# sketch.net
KiCad netlist of a schematic drawn in EAGLE
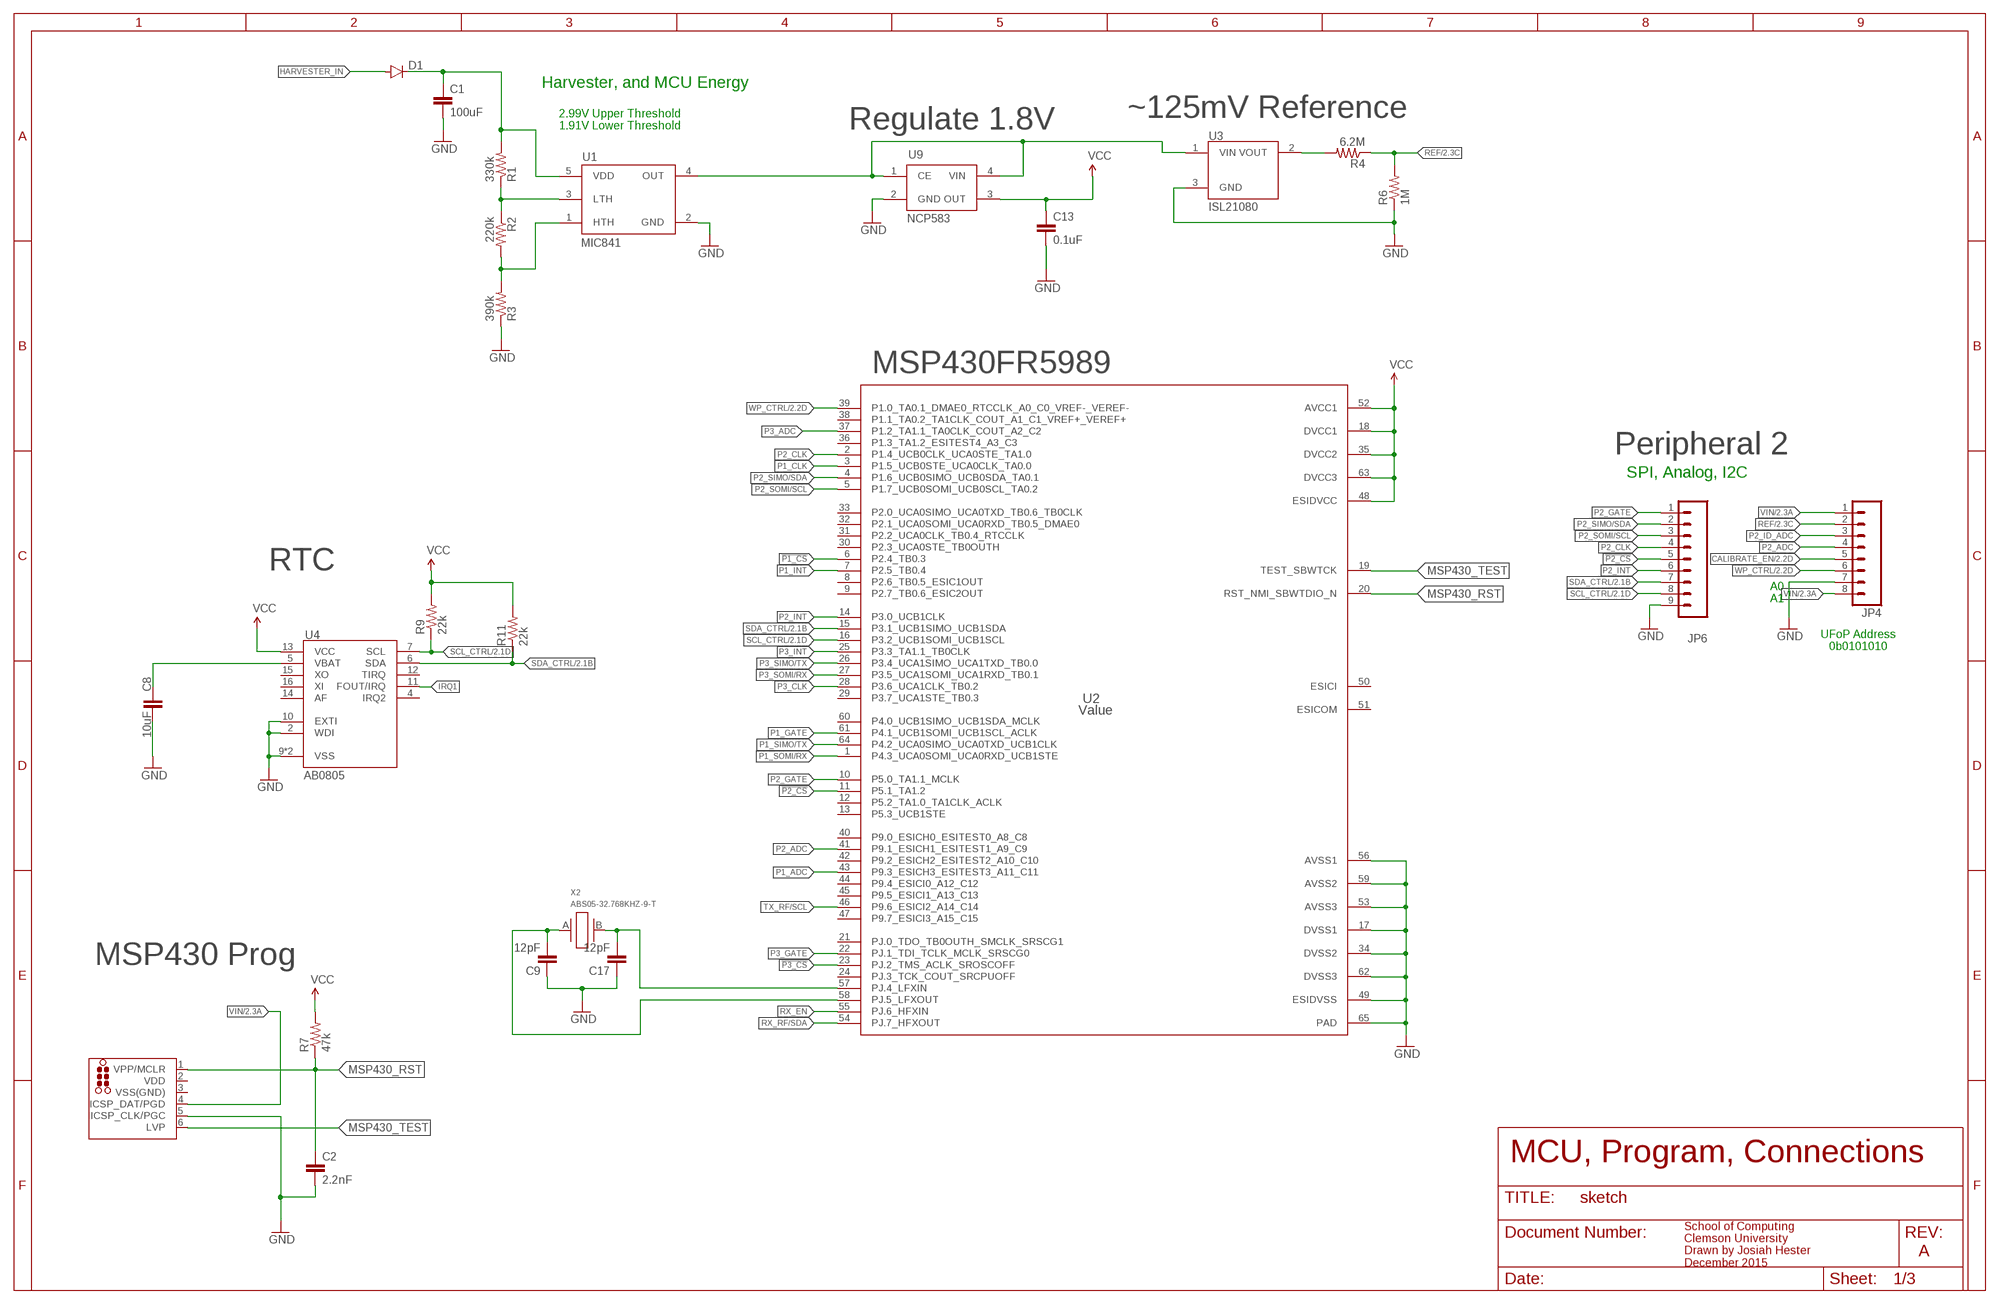
[diagram p0: schematic, sheet 1]
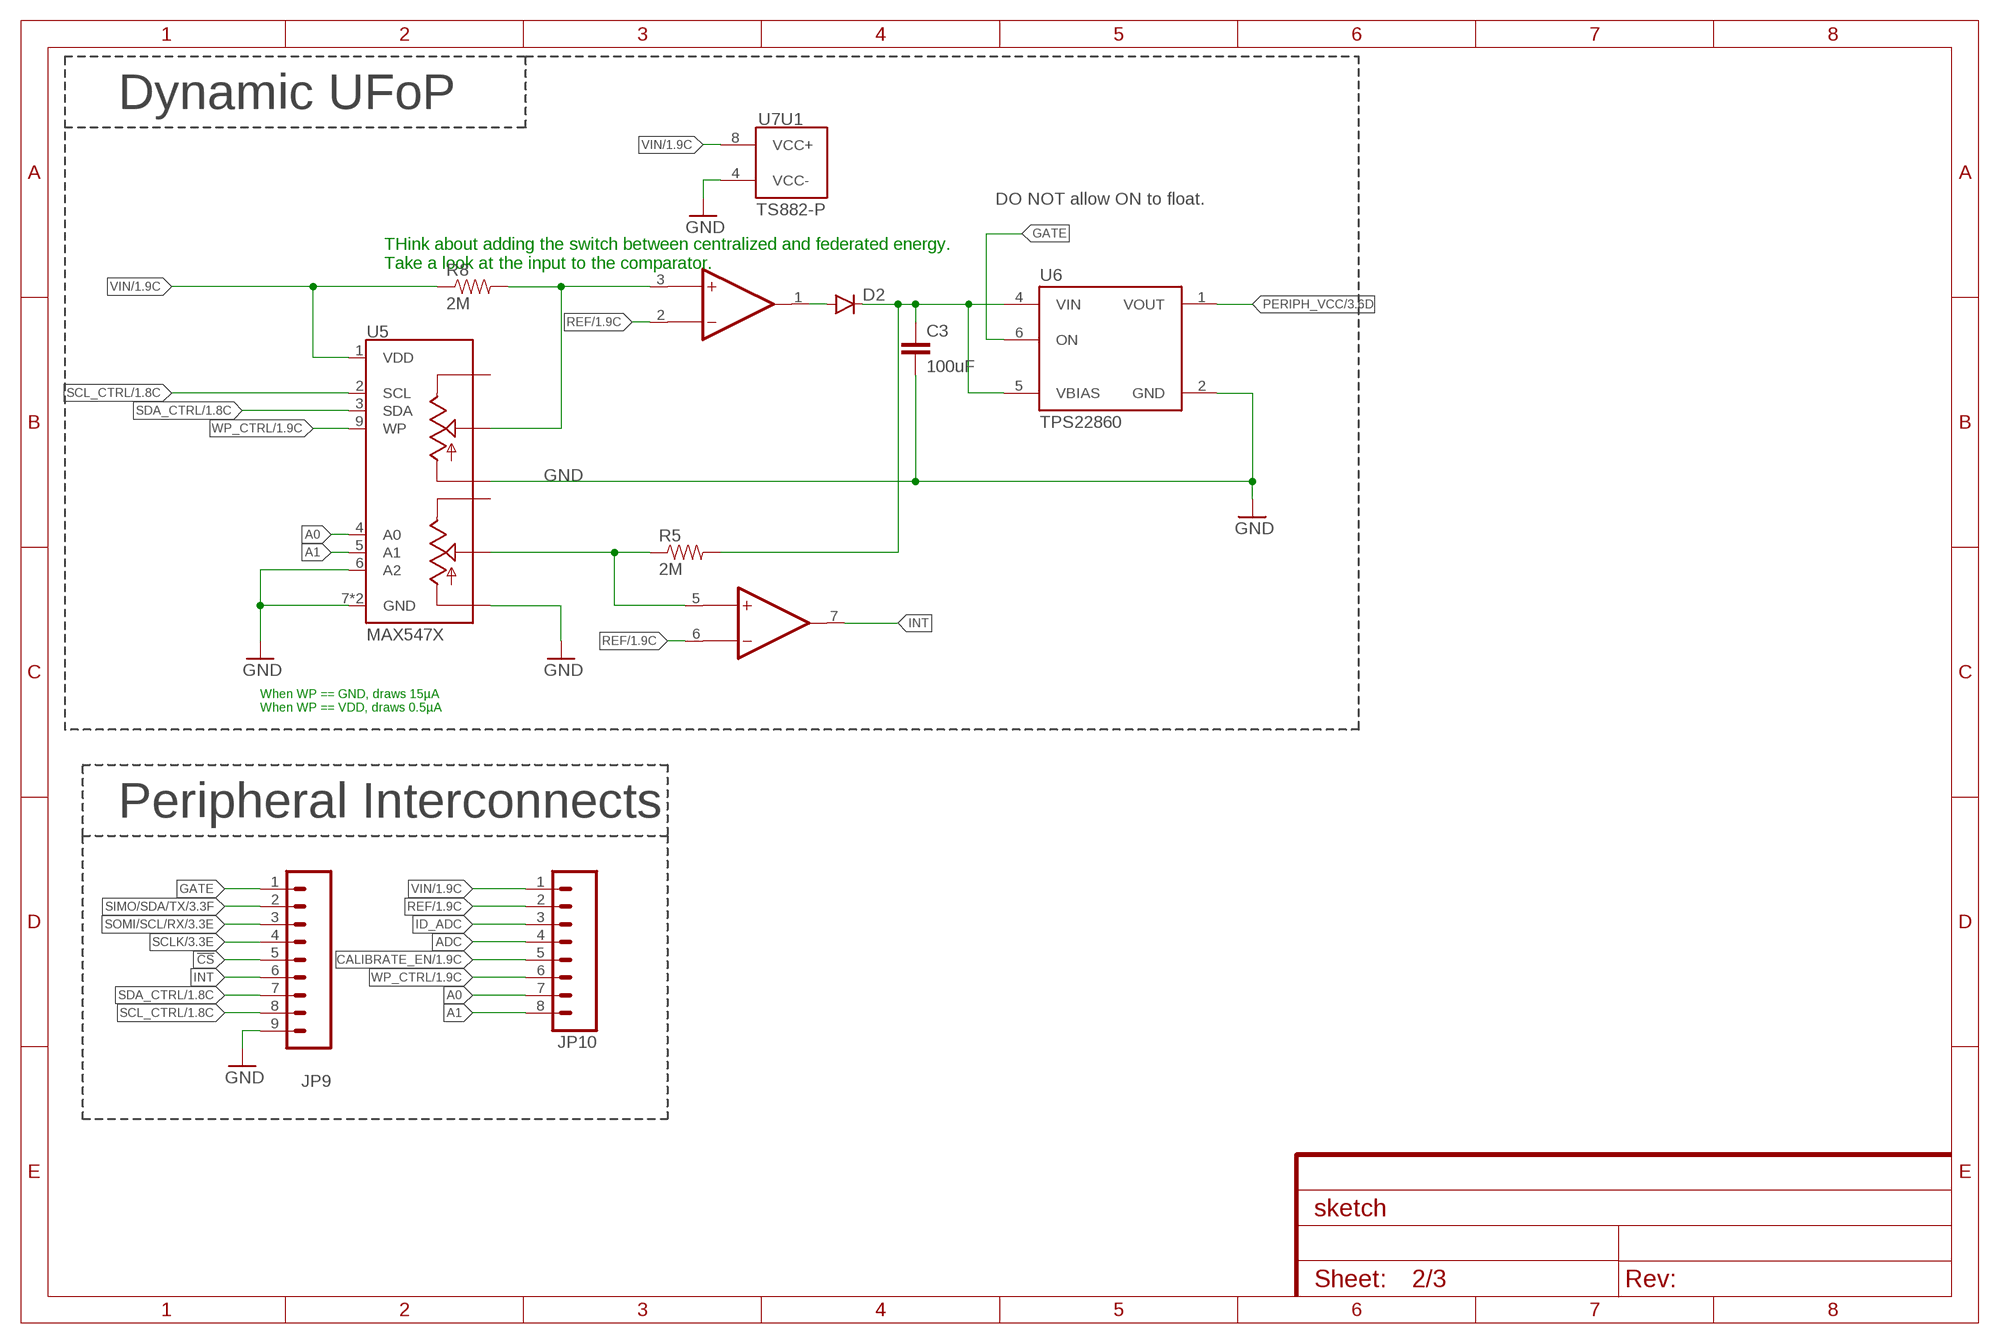
[diagram p1: schematic, sheet 2]
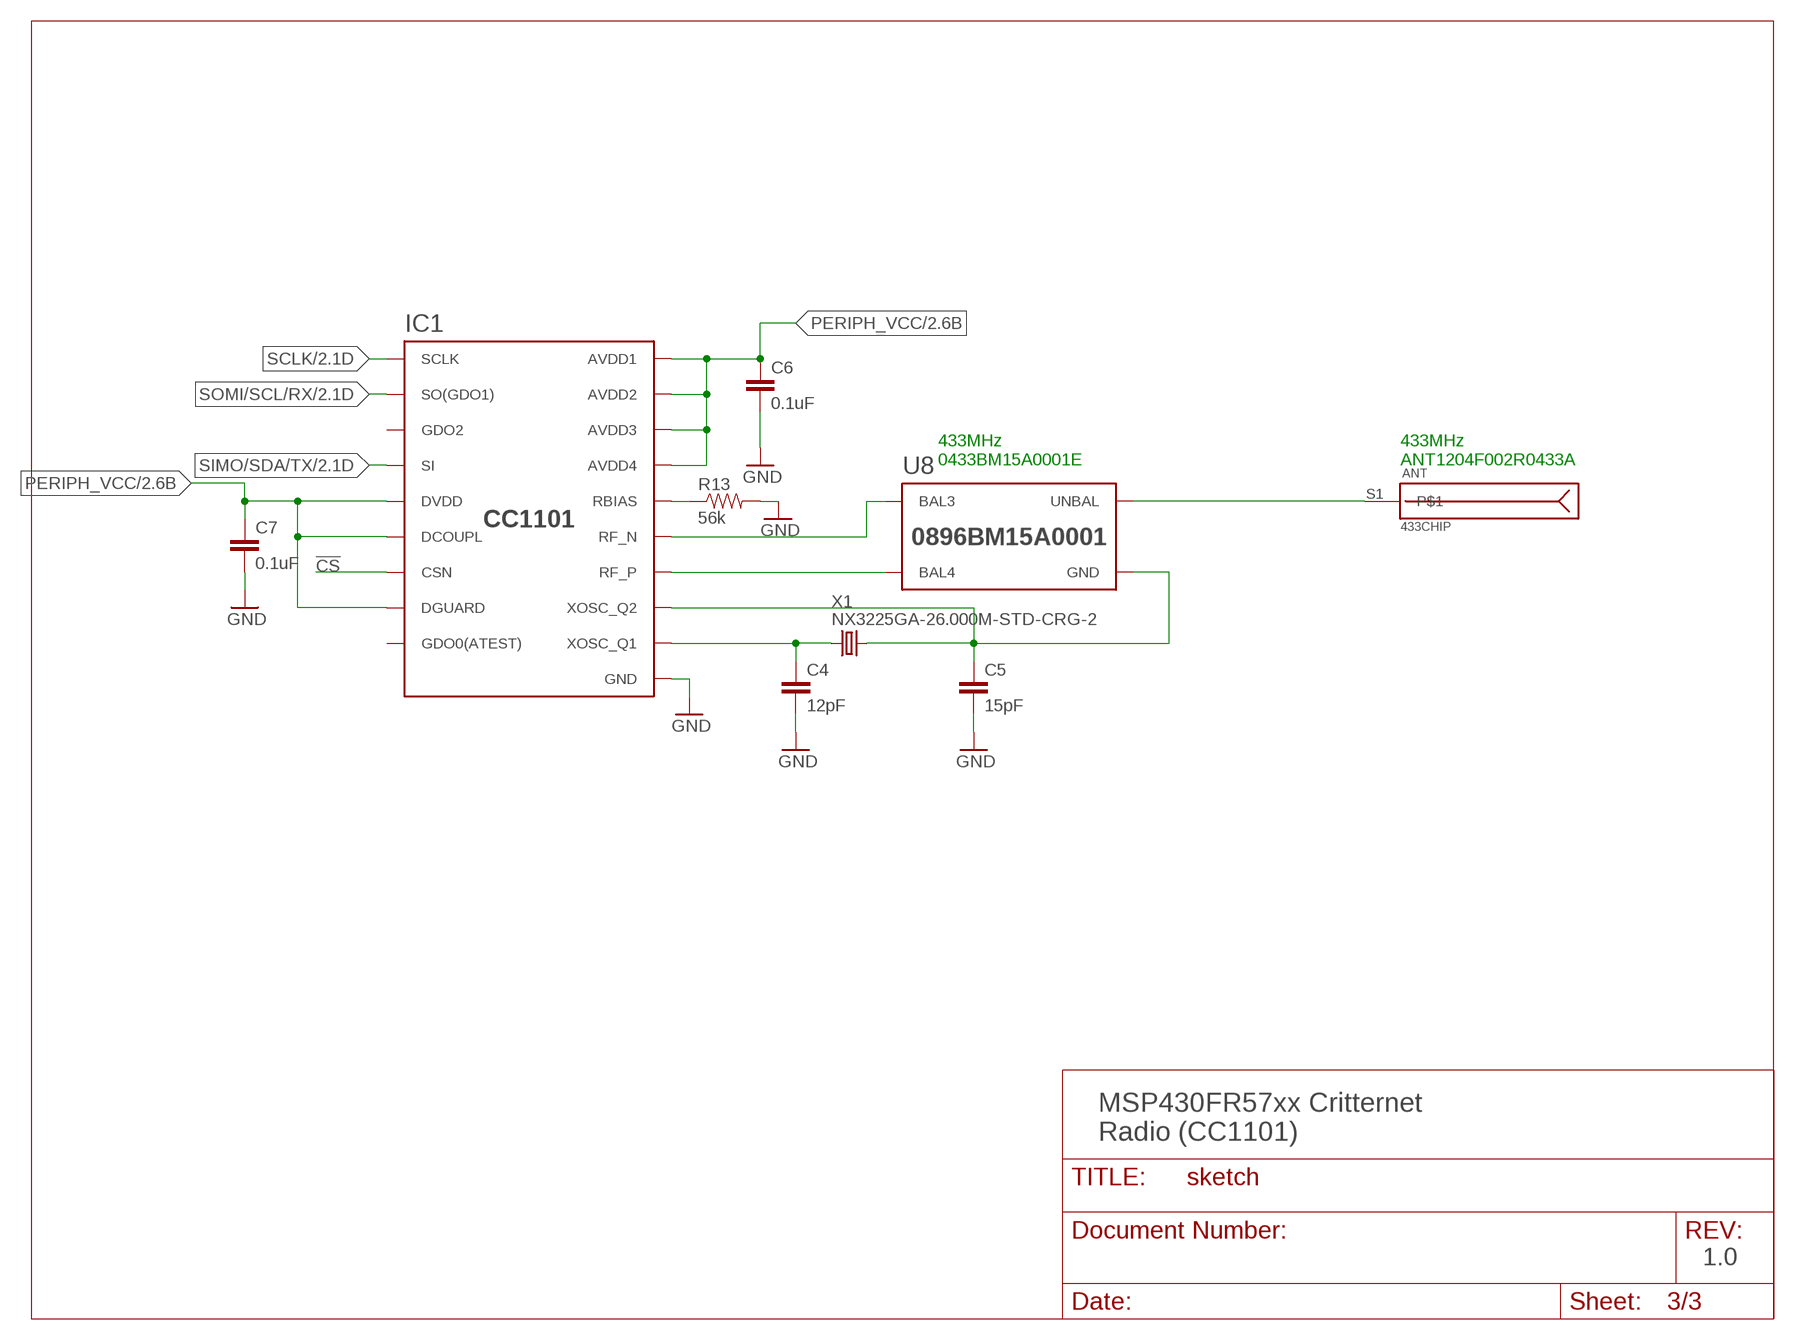
[diagram p2: schematic, sheet 3]

(export (version "E")
  (design (tool "Eeschema 10.0.6"))
  (components
    (comp (ref "C3")
      (value "100uF")
      (footprint "eagle-import:1210")
      (libsource (lib "eagle-import") (part "CAP1210"))
    )
    (comp (ref "D2")
      (value "DIODESOD523")
      (footprint "eagle-import:SOD523")
      (libsource (lib "eagle-import") (part "DIODESOD523"))
    )
    (comp (ref "JP9")
      (value "M091.27MM")
      (footprint "eagle-import:1X09-1.27MM")
      (libsource (lib "eagle-import") (part "M091.27MM"))
    )
    (comp (ref "JP10")
      (value "M081.27MM")
      (footprint "eagle-import:1X08-1.27MM")
      (libsource (lib "eagle-import") (part "M081.27MM"))
    )
    (comp (ref "R5")
      (value "2M")
      (footprint "eagle-import:0603")
      (libsource (lib "eagle-import") (part "R-EU0603"))
    )
    (comp (ref "R8")
      (value "2M")
      (footprint "eagle-import:0603")
      (libsource (lib "eagle-import") (part "R-EU0603"))
    )
    (comp (ref "U5")
      (value "MAX547X")
      (footprint "eagle-import:QFN16")
      (libsource (lib "eagle-import") (part "MAX547X"))
    )
    (comp (ref "U6")
      (value "TPS22860")
      (footprint "eagle-import:TSOT23-6")
      (libsource (lib "eagle-import") (part "TPS22860"))
    )
    (comp (ref "U7")
      (value "TS882-P")
      (footprint "eagle-import:UDFN8")
      (fields (field (name "DIGIKEY") "497-14073-1-ND"))
      (libsource (lib "eagle-import") (part "TS882-P"))
    )
    (comp (ref "ANT")
      (value "433CHIP")
      (footprint "eagle-import:ANT-433-USP")
      (libsource (lib "eagle-import") (part "433CHIP"))
    )
    (comp (ref "C4")
      (value "12pF")
      (footprint "eagle-import:0603")
      (libsource (lib "eagle-import") (part "C-EU0603"))
    )
    (comp (ref "C5")
      (value "15pF")
      (footprint "eagle-import:0603")
      (libsource (lib "eagle-import") (part "C-EU0603"))
    )
    (comp (ref "C6")
      (value "0.1uF")
      (footprint "eagle-import:0603")
      (libsource (lib "eagle-import") (part "C-EU0603"))
    )
    (comp (ref "C7")
      (value "0.1uF")
      (footprint "eagle-import:0603")
      (libsource (lib "eagle-import") (part "C-EU0603"))
    )
    (comp (ref "IC1")
      (value "CC1101")
      (footprint "eagle-import:QLP20")
      (libsource (lib "eagle-import") (part "CC1101"))
    )
    (comp (ref "R13")
      (value "56k")
      (footprint "eagle-import:0603")
      (libsource (lib "eagle-import") (part "R-EU0603"))
    )
    (comp (ref "U8")
      (value "0896BM15A0001")
      (footprint "eagle-import:0896BM15A0001")
      (libsource (lib "eagle-import") (part "0896BM15A0001"))
    )
    (comp (ref "X1")
      (value "NX3225GA-26.000M-STD-CRG-2")
      (footprint "eagle-import:XTAL-3.2X2.5")
      (libsource (lib "eagle-import") (part "XTAL-3.2X2.5"))
    )
    (comp (ref "C1")
      (value "100uF")
      (footprint "eagle-import:1210")
      (libsource (lib "eagle-import") (part "CAP1210"))
    )
    (comp (ref "C2")
      (value "2.2nF")
      (footprint "eagle-import:0603")
      (libsource (lib "eagle-import") (part "C-EU0603"))
    )
    (comp (ref "C8")
      (value "10uF")
      (footprint "eagle-import:C0805")
      (libsource (lib "eagle-import") (part "CAP0805"))
    )
    (comp (ref "C9")
      (value "12pF")
      (footprint "eagle-import:0603")
      (libsource (lib "eagle-import") (part "C-EU0603"))
    )
    (comp (ref "C13")
      (value "0.1uF")
      (footprint "eagle-import:0603")
      (libsource (lib "eagle-import") (part "C-EU0603"))
    )
    (comp (ref "C17")
      (value "12pF")
      (footprint "eagle-import:0603")
      (libsource (lib "eagle-import") (part "C-EU0603"))
    )
    (comp (ref "D1")
      (value "DIODESOD523")
      (footprint "eagle-import:SOD523")
      (libsource (lib "eagle-import") (part "DIODESOD523"))
    )
    (comp (ref "J1")
      (value "TC2030-MCP-NL")
      (footprint "eagle-import:TC2030-MCP-NL")
      (libsource (lib "eagle-import") (part "TC2030-MCP-NL"))
    )
    (comp (ref "JP4")
      (value "M081.27MM")
      (footprint "eagle-import:1X08-1.27MM")
      (libsource (lib "eagle-import") (part "M081.27MM"))
    )
    (comp (ref "JP6")
      (value "M091.27MM")
      (footprint "eagle-import:1X09-1.27MM")
      (libsource (lib "eagle-import") (part "M091.27MM"))
    )
    (comp (ref "R1")
      (value "330k")
      (footprint "eagle-import:0603")
      (libsource (lib "eagle-import") (part "R-EU0603"))
    )
    (comp (ref "R2")
      (value "220k")
      (footprint "eagle-import:0603")
      (libsource (lib "eagle-import") (part "R-EU0603"))
    )
    (comp (ref "R3")
      (value "390k")
      (footprint "eagle-import:0603")
      (libsource (lib "eagle-import") (part "R-EU0603"))
    )
    (comp (ref "R4")
      (value "6.2M")
      (footprint "eagle-import:0603")
      (libsource (lib "eagle-import") (part "R-EU0603"))
    )
    (comp (ref "R6")
      (value "1M")
      (footprint "eagle-import:0603")
      (libsource (lib "eagle-import") (part "R-EU0603"))
    )
    (comp (ref "R7")
      (value "47k")
      (footprint "eagle-import:0603")
      (libsource (lib "eagle-import") (part "R-EU0603"))
    )
    (comp (ref "R9")
      (value "22k")
      (footprint "eagle-import:0603")
      (libsource (lib "eagle-import") (part "R-EU0603"))
    )
    (comp (ref "R11")
      (value "22k")
      (footprint "eagle-import:0603")
      (libsource (lib "eagle-import") (part "R-EU0603"))
    )
    (comp (ref "U1")
      (value "MIC841")
      (footprint "eagle-import:SC70-5")
      (libsource (lib "eagle-import") (part "MIC841"))
    )
    (comp (ref "U2")
      (value "Value")
      (footprint "eagle-import:RGC0064B")
      (fields
        (field (name "ALTERNATEPARTNUMBER") "MSP430FR5989IRGCT")
        (field (name "MANUFACTURER") "Texas Instruments")
        (field (name "PARTNUMBER") "MSP430FR5989IRGCR")
      )
      (libsource (lib "eagle-import") (part "MSP430FR5989IRGCR"))
    )
    (comp (ref "U3")
      (value "ISL21080")
      (footprint "eagle-import:SOT-23")
      (libsource (lib "eagle-import") (part "ISL21080"))
    )
    (comp (ref "U4")
      (value "AB0805")
      (footprint "eagle-import:QFN16")
      (libsource (lib "eagle-import") (part "AB0805"))
    )
    (comp (ref "U9")
      (value "NCP583")
      (footprint "eagle-import:SC82-AB_1PRIMARY")
      (libsource (lib "eagle-import") (part "NCP583"))
    )
    (comp (ref "X2")
      (value "ABS05-32.768KHZ-9-T")
      (footprint "eagle-import:ABS05")
      (libsource (lib "eagle-import") (part "ABS05-32.768KHZ-9-T"))
    )
  )
  (nets
    (net (code "1") (name "A0") (class "Default")
      (node (ref "JP10") (pin "7") (pinfunction "7_7") (pintype "passive"))
      (node (ref "U5") (pin "4") (pinfunction "A0_4") (pintype "bidirectional"))
    )
    (net (code "2") (name "A1") (class "Default")
      (node (ref "JP10") (pin "8") (pinfunction "8_8") (pintype "passive"))
      (node (ref "U5") (pin "5") (pinfunction "A1_5") (pintype "bidirectional"))
    )
    (net (code "3") (name "ADC") (class "Default")
      (node (ref "JP10") (pin "4") (pinfunction "4_4") (pintype "passive"))
    )
    (net (code "4") (name "CALIBRATE_EN") (class "Default")
      (node (ref "JP10") (pin "5") (pinfunction "5_5") (pintype "passive"))
      (node (ref "JP4") (pin "5") (pinfunction "5_5") (pintype "passive"))
    )
    (net (code "5") (name "GATE") (class "Default")
      (node (ref "JP9") (pin "1") (pinfunction "1_1") (pintype "passive"))
      (node (ref "U6") (pin "6") (pinfunction "ON_6") (pintype "bidirectional"))
    )
    (net (code "6") (name "GND") (class "Default")
      (node (ref "C1") (pin "2") (pinfunction "2_2") (pintype "passive"))
      (node (ref "C13") (pin "2") (pinfunction "2_2") (pintype "passive"))
      (node (ref "C17") (pin "1") (pinfunction "1_1") (pintype "passive"))
      (node (ref "C2") (pin "2") (pinfunction "2_2") (pintype "passive"))
      (node (ref "C3") (pin "2") (pinfunction "2_2") (pintype "passive"))
      (node (ref "C4") (pin "2") (pinfunction "2_2") (pintype "passive"))
      (node (ref "C5") (pin "2") (pinfunction "2_2") (pintype "passive"))
      (node (ref "C6") (pin "2") (pinfunction "2_2") (pintype "passive"))
      (node (ref "C7") (pin "2") (pinfunction "2_2") (pintype "passive"))
      (node (ref "C8") (pin "2") (pinfunction "2_2") (pintype "passive"))
      (node (ref "C9") (pin "1") (pinfunction "1_1") (pintype "passive"))
      (node (ref "IC1") (pin "16") (pinfunction "GND_16") (pintype "bidirectional"))
      (node (ref "IC1") (pin "19") (pinfunction "GND_19") (pintype "bidirectional"))
      (node (ref "IC1") (pin "GND") (pinfunction "GND_GND") (pintype "bidirectional"))
      (node (ref "J1") (pin "5") (pinfunction "ICSP_CLK/PGC_5") (pintype "output"))
      (node (ref "JP4") (pin "7") (pinfunction "7_7") (pintype "passive"))
      (node (ref "JP6") (pin "9") (pinfunction "9_9") (pintype "passive"))
      (node (ref "JP9") (pin "9") (pinfunction "9_9") (pintype "passive"))
      (node (ref "R13") (pin "2") (pinfunction "2_2") (pintype "passive"))
      (node (ref "R3") (pin "1") (pinfunction "1_1") (pintype "passive"))
      (node (ref "R6") (pin "1") (pinfunction "1_1") (pintype "passive"))
      (node (ref "U1") (pin "2") (pinfunction "GND_2") (pintype "bidirectional"))
      (node (ref "U2") (pin "17") (pinfunction "DVSS1_17") (pintype "power_in"))
      (node (ref "U2") (pin "34") (pinfunction "DVSS2_34") (pintype "power_in"))
      (node (ref "U2") (pin "49") (pinfunction "ESIDVSS_49") (pintype "power_in"))
      (node (ref "U2") (pin "53") (pinfunction "AVSS3_53") (pintype "power_in"))
      (node (ref "U2") (pin "56") (pinfunction "AVSS1_56") (pintype "power_in"))
      (node (ref "U2") (pin "59") (pinfunction "AVSS2_59") (pintype "power_in"))
      (node (ref "U2") (pin "62") (pinfunction "DVSS3_62") (pintype "power_in"))
      (node (ref "U2") (pin "65") (pinfunction "PAD_65") (pintype "power_in"))
      (node (ref "U3") (pin "3") (pinfunction "GND_3") (pintype "bidirectional"))
      (node (ref "U4") (pin "10") (pinfunction "EXTI_10") (pintype "bidirectional"))
      (node (ref "U4") (pin "2") (pinfunction "WDI_2") (pintype "bidirectional"))
      (node (ref "U4") (pin "9") (pinfunction "VSS_9") (pintype "bidirectional"))
      (node (ref "U4") (pin "TH") (pinfunction "VSS_TH") (pintype "bidirectional"))
      (node (ref "U5") (pin "10") (pinfunction "LB_10") (pintype "bidirectional"))
      (node (ref "U5") (pin "13") (pinfunction "LA_13") (pintype "passive"))
      (node (ref "U5") (pin "6") (pinfunction "A2_6") (pintype "bidirectional"))
      (node (ref "U5") (pin "7") (pinfunction "GND_7") (pintype "bidirectional"))
      (node (ref "U5") (pin "TH") (pinfunction "GND_TH") (pintype "bidirectional"))
      (node (ref "U6") (pin "2") (pinfunction "GND_2") (pintype "bidirectional"))
      (node (ref "U7") (pin "4") (pinfunction "VCC-_4") (pintype "bidirectional"))
      (node (ref "U9") (pin "2") (pinfunction "GND_2") (pintype "bidirectional"))
    )
    (net (code "7") (name "HARVESTER_IN") (class "Default")
      (node (ref "C1") (pin "1") (pinfunction "1_1") (pintype "passive"))
      (node (ref "D1") (pin "A") (pinfunction "A_A") (pintype "passive"))
      (node (ref "D1") (pin "C") (pinfunction "C_C") (pintype "passive"))
      (node (ref "R1") (pin "2") (pinfunction "2_2") (pintype "passive"))
      (node (ref "U1") (pin "5") (pinfunction "VDD_5") (pintype "bidirectional"))
    )
    (net (code "8") (name "ID_ADC") (class "Default")
      (node (ref "JP10") (pin "3") (pinfunction "3_3") (pintype "passive"))
    )
    (net (code "9") (name "INT") (class "Default")
      (node (ref "JP9") (pin "6") (pinfunction "6_6") (pintype "passive"))
      (node (ref "U7") (pin "7") (pinfunction "OUT1_7") (pintype "output"))
    )
    (net (code "10") (name "IRQ1") (class "Default")
      (node (ref "U4") (pin "11") (pinfunction "FOUT/IRQ_11") (pintype "bidirectional"))
    )
    (net (code "11") (name "MSP430_RST") (class "Default")
      (node (ref "C2") (pin "1") (pinfunction "1_1") (pintype "passive"))
      (node (ref "J1") (pin "1") (pinfunction "VPP/MCLR_1") (pintype "passive"))
      (node (ref "R7") (pin "1") (pinfunction "1_1") (pintype "passive"))
      (node (ref "U2") (pin "20") (pinfunction "RST_NMI_SBWTDIO_N_20") (pintype "bidirectional"))
    )
    (net (code "12") (name "MSP430_TEST") (class "Default")
      (node (ref "J1") (pin "6") (pinfunction "LVP_6") (pintype "bidirectional"))
      (node (ref "U2") (pin "19") (pinfunction "TEST_SBWTCK_19") (pintype "input"))
    )
    (net (code "13") (name "Net-(ANT-P$1)") (class "Default")
      (node (ref "ANT") (pin "S1") (pinfunction "P$1_S1") (pintype "bidirectional"))
      (node (ref "U8") (pin "1") (pinfunction "UNBAL_1") (pintype "bidirectional"))
    )
    (net (code "14") (name "Net-(IC1-RBIAS)") (class "Default")
      (node (ref "IC1") (pin "17") (pinfunction "RBIAS_17") (pintype "bidirectional"))
      (node (ref "R13") (pin "1") (pinfunction "1_1") (pintype "passive"))
    )
    (net (code "15") (name "Net-(IC1-RF_N)") (class "Default")
      (node (ref "IC1") (pin "13") (pinfunction "RF_N_13") (pintype "bidirectional"))
      (node (ref "U8") (pin "3") (pinfunction "BAL3_3") (pintype "bidirectional"))
    )
    (net (code "16") (name "Net-(IC1-RF_P)") (class "Default")
      (node (ref "IC1") (pin "12") (pinfunction "RF_P_12") (pintype "bidirectional"))
      (node (ref "U8") (pin "4") (pinfunction "BAL4_4") (pintype "bidirectional"))
    )
    (net (code "17") (name "Net-(IC1-XOSC_Q1)") (class "Default")
      (node (ref "C4") (pin "1") (pinfunction "1_1") (pintype "passive"))
      (node (ref "IC1") (pin "8") (pinfunction "XOSC_Q1_8") (pintype "bidirectional"))
      (node (ref "X1") (pin "1") (pinfunction "1_1") (pintype "passive"))
    )
    (net (code "18") (name "Net-(IC1-XOSC_Q2)") (class "Default")
      (node (ref "C5") (pin "1") (pinfunction "1_1") (pintype "passive"))
      (node (ref "IC1") (pin "10") (pinfunction "XOSC_Q2_10") (pintype "bidirectional"))
      (node (ref "U8") (pin "2") (pinfunction "GND_2") (pintype "bidirectional"))
      (node (ref "U8") (pin "5") (pinfunction "GND_5") (pintype "bidirectional"))
      (node (ref "U8") (pin "6") (pinfunction "GND_6") (pintype "bidirectional"))
      (node (ref "X1") (pin "3") (pinfunction "2_3") (pintype "passive"))
    )
    (net (code "19") (name "Net-(U1-HTH)") (class "Default")
      (node (ref "R2") (pin "2") (pinfunction "2_2") (pintype "passive"))
      (node (ref "R3") (pin "2") (pinfunction "2_2") (pintype "passive"))
      (node (ref "U1") (pin "1") (pinfunction "HTH_1") (pintype "bidirectional"))
    )
    (net (code "20") (name "Net-(U1-LTH)") (class "Default")
      (node (ref "R1") (pin "1") (pinfunction "1_1") (pintype "passive"))
      (node (ref "R2") (pin "1") (pinfunction "1_1") (pintype "passive"))
      (node (ref "U1") (pin "3") (pinfunction "LTH_3") (pintype "bidirectional"))
    )
    (net (code "21") (name "Net-(U2-PJ.4_LFXIN)") (class "Default")
      (node (ref "C17") (pin "2") (pinfunction "2_2") (pintype "passive"))
      (node (ref "U2") (pin "57") (pinfunction "PJ.4_LFXIN_57") (pintype "bidirectional"))
      (node (ref "X2") (pin "B") (pinfunction "2_B") (pintype "bidirectional"))
    )
    (net (code "22") (name "Net-(U2-PJ.5_LFXOUT)") (class "Default")
      (node (ref "C9") (pin "2") (pinfunction "2_2") (pintype "passive"))
      (node (ref "U2") (pin "58") (pinfunction "PJ.5_LFXOUT_58") (pintype "bidirectional"))
      (node (ref "X2") (pin "A") (pinfunction "1_A") (pintype "bidirectional"))
    )
    (net (code "23") (name "Net-(U3-VOUT)") (class "Default")
      (node (ref "R4") (pin "2") (pinfunction "2_2") (pintype "passive"))
      (node (ref "U3") (pin "2") (pinfunction "VOUT_2") (pintype "bidirectional"))
    )
    (net (code "24") (name "Net-(U4-VBAT)") (class "Default")
      (node (ref "C8") (pin "1") (pinfunction "1_1") (pintype "passive"))
      (node (ref "U4") (pin "5") (pinfunction "VBAT_5") (pintype "bidirectional"))
    )
    (net (code "25") (name "Net-(U5-WA)") (class "Default")
      (node (ref "R8") (pin "2") (pinfunction "2_2") (pintype "passive"))
      (node (ref "U5") (pin "14") (pinfunction "WA_14") (pintype "passive"))
      (node (ref "U7") (pin "3") (pinfunction "IN1+_3") (pintype "input"))
    )
    (net (code "26") (name "Net-(U5-WB)") (class "Default")
      (node (ref "R5") (pin "1") (pinfunction "1_1") (pintype "passive"))
      (node (ref "U5") (pin "11") (pinfunction "WB_11") (pintype "bidirectional"))
      (node (ref "U7") (pin "5") (pinfunction "IN1+_5") (pintype "input"))
    )
    (net (code "27") (name "Net-(U6-VBIAS)") (class "Default")
      (node (ref "C3") (pin "1") (pinfunction "1_1") (pintype "passive"))
      (node (ref "D2") (pin "C") (pinfunction "C_C") (pintype "passive"))
      (node (ref "R5") (pin "2") (pinfunction "2_2") (pintype "passive"))
      (node (ref "U6") (pin "4") (pinfunction "VIN_4") (pintype "bidirectional"))
      (node (ref "U6") (pin "5") (pinfunction "VBIAS_5") (pintype "bidirectional"))
    )
    (net (code "28") (name "Net-(U7A-OUT1)") (class "Default")
      (node (ref "D2") (pin "A") (pinfunction "A_A") (pintype "passive"))
      (node (ref "U7") (pin "1") (pinfunction "OUT1_1") (pintype "output"))
    )
    (net (code "29") (name "P1_ADC") (class "Default")
      (node (ref "U2") (pin "43") (pinfunction "P9.3_ESICH3_ESITEST3_A11_C11_43") (pintype "bidirectional"))
    )
    (net (code "30") (name "P1_CLK") (class "Default")
      (node (ref "U2") (pin "3") (pinfunction "P1.5_UCB0STE_UCA0CLK_TA0.0_3") (pintype "bidirectional"))
    )
    (net (code "31") (name "P1_GATE") (class "Default")
      (node (ref "U2") (pin "61") (pinfunction "P4.1_UCB1SOMI_UCB1SCL_ACLK_61") (pintype "bidirectional"))
    )
    (net (code "32") (name "P1_INT") (class "Default")
      (node (ref "U2") (pin "7") (pinfunction "P2.5_TB0.4_7") (pintype "bidirectional"))
    )
    (net (code "33") (name "P1_SIMO{slash}TX") (class "Default")
      (node (ref "U2") (pin "64") (pinfunction "P4.2_UCA0SIMO_UCA0TXD_UCB1CLK_64") (pintype "bidirectional"))
    )
    (net (code "34") (name "P1_SOMI{slash}RX") (class "Default")
      (node (ref "U2") (pin "1") (pinfunction "P4.3_UCA0SOMI_UCA0RXD_UCB1STE_1") (pintype "bidirectional"))
    )
    (net (code "35") (name "P2_ADC") (class "Default")
      (node (ref "JP4") (pin "4") (pinfunction "4_4") (pintype "passive"))
      (node (ref "U2") (pin "41") (pinfunction "P9.1_ESICH1_ESITEST1_A9_C9_41") (pintype "bidirectional"))
    )
    (net (code "36") (name "P2_CLK") (class "Default")
      (node (ref "JP6") (pin "4") (pinfunction "4_4") (pintype "passive"))
      (node (ref "U2") (pin "2") (pinfunction "P1.4_UCB0CLK_UCA0STE_TA1.0_2") (pintype "bidirectional"))
    )
    (net (code "37") (name "P2_GATE") (class "Default")
      (node (ref "JP6") (pin "1") (pinfunction "1_1") (pintype "passive"))
      (node (ref "U2") (pin "10") (pinfunction "P5.0_TA1.1_MCLK_10") (pintype "bidirectional"))
    )
    (net (code "38") (name "P2_ID_ADC") (class "Default")
      (node (ref "JP4") (pin "3") (pinfunction "3_3") (pintype "passive"))
    )
    (net (code "39") (name "P2_INT") (class "Default")
      (node (ref "JP6") (pin "6") (pinfunction "6_6") (pintype "passive"))
      (node (ref "U2") (pin "14") (pinfunction "P3.0_UCB1CLK_14") (pintype "bidirectional"))
    )
    (net (code "40") (name "P2_SIMO{slash}SDA") (class "Default")
      (node (ref "JP6") (pin "2") (pinfunction "2_2") (pintype "passive"))
      (node (ref "U2") (pin "4") (pinfunction "P1.6_UCB0SIMO_UCB0SDA_TA0.1_4") (pintype "bidirectional"))
    )
    (net (code "41") (name "P2_SOMI{slash}SCL") (class "Default")
      (node (ref "JP6") (pin "3") (pinfunction "3_3") (pintype "passive"))
      (node (ref "U2") (pin "5") (pinfunction "P1.7_UCB0SOMI_UCB0SCL_TA0.2_5") (pintype "bidirectional"))
    )
    (net (code "42") (name "P3_ADC") (class "Default")
      (node (ref "U2") (pin "37") (pinfunction "P1.2_TA1.1_TA0CLK_COUT_A2_C2_37") (pintype "bidirectional"))
    )
    (net (code "43") (name "P3_CLK") (class "Default")
      (node (ref "U2") (pin "28") (pinfunction "P3.6_UCA1CLK_TB0.2_28") (pintype "bidirectional"))
    )
    (net (code "44") (name "P3_GATE") (class "Default")
      (node (ref "U2") (pin "22") (pinfunction "PJ.1_TDI_TCLK_MCLK_SRSCG0_22") (pintype "bidirectional"))
    )
    (net (code "45") (name "P3_INT") (class "Default")
      (node (ref "U2") (pin "25") (pinfunction "P3.3_TA1.1_TB0CLK_25") (pintype "bidirectional"))
    )
    (net (code "46") (name "P3_SIMO{slash}TX") (class "Default")
      (node (ref "U2") (pin "26") (pinfunction "P3.4_UCA1SIMO_UCA1TXD_TB0.0_26") (pintype "bidirectional"))
    )
    (net (code "47") (name "P3_SOMI{slash}RX") (class "Default")
      (node (ref "U2") (pin "27") (pinfunction "P3.5_UCA1SOMI_UCA1RXD_TB0.1_27") (pintype "bidirectional"))
    )
    (net (code "48") (name "PERIPH_VCC") (class "Default")
      (node (ref "C6") (pin "1") (pinfunction "1_1") (pintype "passive"))
      (node (ref "C7") (pin "1") (pinfunction "1_1") (pintype "passive"))
      (node (ref "IC1") (pin "11") (pinfunction "AVDD2_11") (pintype "bidirectional"))
      (node (ref "IC1") (pin "14") (pinfunction "AVDD3_14") (pintype "bidirectional"))
      (node (ref "IC1") (pin "15") (pinfunction "AVDD4_15") (pintype "bidirectional"))
      (node (ref "IC1") (pin "18") (pinfunction "DGUARD_18") (pintype "bidirectional"))
      (node (ref "IC1") (pin "4") (pinfunction "DVDD_4") (pintype "bidirectional"))
      (node (ref "IC1") (pin "5") (pinfunction "DCOUPL_5") (pintype "bidirectional"))
      (node (ref "IC1") (pin "9") (pinfunction "AVDD1_9") (pintype "bidirectional"))
      (node (ref "U6") (pin "1") (pinfunction "VOUT_1") (pintype "bidirectional"))
    )
    (net (code "49") (name "REF") (class "Default")
      (node (ref "JP10") (pin "2") (pinfunction "2_2") (pintype "passive"))
      (node (ref "JP4") (pin "2") (pinfunction "2_2") (pintype "passive"))
      (node (ref "R4") (pin "1") (pinfunction "1_1") (pintype "passive"))
      (node (ref "R6") (pin "2") (pinfunction "2_2") (pintype "passive"))
      (node (ref "U7") (pin "2") (pinfunction "IN1-_2") (pintype "input"))
      (node (ref "U7") (pin "6") (pinfunction "IN1-_6") (pintype "input"))
    )
    (net (code "50") (name "RX_EN") (class "Default")
      (node (ref "U2") (pin "55") (pinfunction "PJ.6_HFXIN_55") (pintype "bidirectional"))
    )
    (net (code "51") (name "RX_RF{slash}SDA") (class "Default")
      (node (ref "U2") (pin "54") (pinfunction "PJ.7_HFXOUT_54") (pintype "bidirectional"))
    )
    (net (code "52") (name "SCLK") (class "Default")
      (node (ref "IC1") (pin "1") (pinfunction "SCLK_1") (pintype "bidirectional"))
      (node (ref "JP9") (pin "4") (pinfunction "4_4") (pintype "passive"))
    )
    (net (code "53") (name "SCL_CTRL") (class "Default")
      (node (ref "JP6") (pin "8") (pinfunction "8_8") (pintype "passive"))
      (node (ref "JP9") (pin "8") (pinfunction "8_8") (pintype "passive"))
      (node (ref "R9") (pin "1") (pinfunction "1_1") (pintype "passive"))
      (node (ref "U2") (pin "16") (pinfunction "P3.2_UCB1SOMI_UCB1SCL_16") (pintype "bidirectional"))
      (node (ref "U4") (pin "7") (pinfunction "SCL_7") (pintype "bidirectional"))
      (node (ref "U5") (pin "2") (pinfunction "SCL_2") (pintype "bidirectional"))
    )
    (net (code "54") (name "SDA_CTRL") (class "Default")
      (node (ref "JP6") (pin "7") (pinfunction "7_7") (pintype "passive"))
      (node (ref "JP9") (pin "7") (pinfunction "7_7") (pintype "passive"))
      (node (ref "R11") (pin "1") (pinfunction "1_1") (pintype "passive"))
      (node (ref "U2") (pin "15") (pinfunction "P3.1_UCB1SIMO_UCB1SDA_15") (pintype "bidirectional"))
      (node (ref "U4") (pin "6") (pinfunction "SDA_6") (pintype "bidirectional"))
      (node (ref "U5") (pin "3") (pinfunction "SDA_3") (pintype "bidirectional"))
    )
    (net (code "55") (name "SIMO{slash}SDA{slash}TX") (class "Default")
      (node (ref "IC1") (pin "20") (pinfunction "SI_20") (pintype "bidirectional"))
      (node (ref "JP9") (pin "2") (pinfunction "2_2") (pintype "passive"))
    )
    (net (code "56") (name "SOMI{slash}SCL{slash}RX") (class "Default")
      (node (ref "IC1") (pin "2") (pinfunction "SO(GDO1)_2") (pintype "bidirectional"))
      (node (ref "JP9") (pin "3") (pinfunction "3_3") (pintype "passive"))
    )
    (net (code "57") (name "TX_RF{slash}SCL") (class "Default")
      (node (ref "U2") (pin "46") (pinfunction "P9.6_ESICI2_A14_C14_46") (pintype "bidirectional"))
    )
    (net (code "58") (name "VCC") (class "Default")
      (node (ref "C13") (pin "1") (pinfunction "1_1") (pintype "passive"))
      (node (ref "R11") (pin "2") (pinfunction "2_2") (pintype "passive"))
      (node (ref "R7") (pin "2") (pinfunction "2_2") (pintype "passive"))
      (node (ref "R9") (pin "2") (pinfunction "2_2") (pintype "passive"))
      (node (ref "U2") (pin "18") (pinfunction "DVCC1_18") (pintype "power_in"))
      (node (ref "U2") (pin "35") (pinfunction "DVCC2_35") (pintype "power_in"))
      (node (ref "U2") (pin "48") (pinfunction "ESIDVCC_48") (pintype "power_in"))
      (node (ref "U2") (pin "52") (pinfunction "AVCC1_52") (pintype "power_in"))
      (node (ref "U2") (pin "63") (pinfunction "DVCC3_63") (pintype "power_in"))
      (node (ref "U4") (pin "13") (pinfunction "VCC_13") (pintype "bidirectional"))
      (node (ref "U9") (pin "3") (pinfunction "OUT_3") (pintype "bidirectional"))
    )
    (net (code "59") (name "VDD") (class "Default")
      (node (ref "J1") (pin "2") (pinfunction "VDD_2") (pintype "power_in"))
    )
    (net (code "60") (name "VIN") (class "Default")
      (node (ref "J1") (pin "4") (pinfunction "ICSP_DAT/PGD_4") (pintype "bidirectional"))
      (node (ref "JP10") (pin "1") (pinfunction "1_1") (pintype "passive"))
      (node (ref "JP4") (pin "1") (pinfunction "1_1") (pintype "passive"))
      (node (ref "JP4") (pin "8") (pinfunction "8_8") (pintype "passive"))
      (node (ref "R8") (pin "1") (pinfunction "1_1") (pintype "passive"))
      (node (ref "U1") (pin "4") (pinfunction "OUT_4") (pintype "bidirectional"))
      (node (ref "U3") (pin "1") (pinfunction "VIN_1") (pintype "bidirectional"))
      (node (ref "U5") (pin "1") (pinfunction "VDD_1") (pintype "bidirectional"))
      (node (ref "U7") (pin "8") (pinfunction "VCC+_8") (pintype "bidirectional"))
      (node (ref "U9") (pin "1") (pinfunction "CE_1") (pintype "bidirectional"))
      (node (ref "U9") (pin "4") (pinfunction "VIN_4") (pintype "bidirectional"))
    )
    (net (code "61") (name "VSS(GND)") (class "Default")
      (node (ref "J1") (pin "3") (pinfunction "VSS(GND)_3") (pintype "power_in"))
    )
    (net (code "62") (name "WP_CTRL") (class "Default")
      (node (ref "JP10") (pin "6") (pinfunction "6_6") (pintype "passive"))
      (node (ref "JP4") (pin "6") (pinfunction "6_6") (pintype "passive"))
      (node (ref "U2") (pin "39") (pinfunction "P1.0_TA0.1_DMAE0_RTCCLK_A0_C0_VREF-_VEREF-_39") (pintype "bidirectional"))
      (node (ref "U5") (pin "9") (pinfunction "WP_9") (pintype "bidirectional"))
    )
    (net (code "63") (name "unconnected-(IC1-GDO0(ATEST)-Pad6)") (class "Default")
      (node (ref "IC1") (pin "6") (pinfunction "GDO0(ATEST)_6") (pintype "bidirectional"))
    )
    (net (code "64") (name "unconnected-(IC1-GDO2-Pad3)") (class "Default")
      (node (ref "IC1") (pin "3") (pinfunction "GDO2_3") (pintype "bidirectional"))
    )
    (net (code "65") (name "unconnected-(U2-ESICI-Pad50)") (class "Default")
      (node (ref "U2") (pin "50") (pinfunction "ESICI_50") (pintype "input"))
    )
    (net (code "66") (name "unconnected-(U2-ESICOM-Pad51)") (class "Default")
      (node (ref "U2") (pin "51") (pinfunction "ESICOM_51") (pintype "passive"))
    )
    (net (code "67") (name "unconnected-(U2-P1.1_TA0.2_TA1CLK_COUT_A1_C1_VREF+_VEREF+-Pad38)") (class "Default")
      (node (ref "U2") (pin "38") (pinfunction "P1.1_TA0.2_TA1CLK_COUT_A1_C1_VREF+_VEREF+_38") (pintype "bidirectional"))
    )
    (net (code "68") (name "unconnected-(U2-P1.3_TA1.2_ESITEST4_A3_C3-Pad36)") (class "Default")
      (node (ref "U2") (pin "36") (pinfunction "P1.3_TA1.2_ESITEST4_A3_C3_36") (pintype "bidirectional"))
    )
    (net (code "69") (name "unconnected-(U2-P2.0_UCA0SIMO_UCA0TXD_TB0.6_TB0CLK-Pad33)") (class "Default")
      (node (ref "U2") (pin "33") (pinfunction "P2.0_UCA0SIMO_UCA0TXD_TB0.6_TB0CLK_33") (pintype "bidirectional"))
    )
    (net (code "70") (name "unconnected-(U2-P2.1_UCA0SOMI_UCA0RXD_TB0.5_DMAE0-Pad32)") (class "Default")
      (node (ref "U2") (pin "32") (pinfunction "P2.1_UCA0SOMI_UCA0RXD_TB0.5_DMAE0_32") (pintype "bidirectional"))
    )
    (net (code "71") (name "unconnected-(U2-P2.2_UCA0CLK_TB0.4_RTCCLK-Pad31)") (class "Default")
      (node (ref "U2") (pin "31") (pinfunction "P2.2_UCA0CLK_TB0.4_RTCCLK_31") (pintype "bidirectional"))
    )
    (net (code "72") (name "unconnected-(U2-P2.3_UCA0STE_TB0OUTH-Pad30)") (class "Default")
      (node (ref "U2") (pin "30") (pinfunction "P2.3_UCA0STE_TB0OUTH_30") (pintype "bidirectional"))
    )
    (net (code "73") (name "unconnected-(U2-P2.6_TB0.5_ESIC1OUT-Pad8)") (class "Default")
      (node (ref "U2") (pin "8") (pinfunction "P2.6_TB0.5_ESIC1OUT_8") (pintype "bidirectional"))
    )
    (net (code "74") (name "unconnected-(U2-P2.7_TB0.6_ESIC2OUT-Pad9)") (class "Default")
      (node (ref "U2") (pin "9") (pinfunction "P2.7_TB0.6_ESIC2OUT_9") (pintype "bidirectional"))
    )
    (net (code "75") (name "unconnected-(U2-P3.7_UCA1STE_TB0.3-Pad29)") (class "Default")
      (node (ref "U2") (pin "29") (pinfunction "P3.7_UCA1STE_TB0.3_29") (pintype "bidirectional"))
    )
    (net (code "76") (name "unconnected-(U2-P4.0_UCB1SIMO_UCB1SDA_MCLK-Pad60)") (class "Default")
      (node (ref "U2") (pin "60") (pinfunction "P4.0_UCB1SIMO_UCB1SDA_MCLK_60") (pintype "bidirectional"))
    )
    (net (code "77") (name "unconnected-(U2-P5.2_TA1.0_TA1CLK_ACLK-Pad12)") (class "Default")
      (node (ref "U2") (pin "12") (pinfunction "P5.2_TA1.0_TA1CLK_ACLK_12") (pintype "bidirectional"))
    )
    (net (code "78") (name "unconnected-(U2-P5.3_UCB1STE-Pad13)") (class "Default")
      (node (ref "U2") (pin "13") (pinfunction "P5.3_UCB1STE_13") (pintype "bidirectional"))
    )
    (net (code "79") (name "unconnected-(U2-P9.0_ESICH0_ESITEST0_A8_C8-Pad40)") (class "Default")
      (node (ref "U2") (pin "40") (pinfunction "P9.0_ESICH0_ESITEST0_A8_C8_40") (pintype "bidirectional"))
    )
    (net (code "80") (name "unconnected-(U2-P9.2_ESICH2_ESITEST2_A10_C10-Pad42)") (class "Default")
      (node (ref "U2") (pin "42") (pinfunction "P9.2_ESICH2_ESITEST2_A10_C10_42") (pintype "bidirectional"))
    )
    (net (code "81") (name "unconnected-(U2-P9.4_ESICI0_A12_C12-Pad44)") (class "Default")
      (node (ref "U2") (pin "44") (pinfunction "P9.4_ESICI0_A12_C12_44") (pintype "bidirectional"))
    )
    (net (code "82") (name "unconnected-(U2-P9.5_ESICI1_A13_C13-Pad45)") (class "Default")
      (node (ref "U2") (pin "45") (pinfunction "P9.5_ESICI1_A13_C13_45") (pintype "bidirectional"))
    )
    (net (code "83") (name "unconnected-(U2-P9.7_ESICI3_A15_C15-Pad47)") (class "Default")
      (node (ref "U2") (pin "47") (pinfunction "P9.7_ESICI3_A15_C15_47") (pintype "bidirectional"))
    )
    (net (code "84") (name "unconnected-(U2-PJ.0_TDO_TB0OUTH_SMCLK_SRSCG1-Pad21)") (class "Default")
      (node (ref "U2") (pin "21") (pinfunction "PJ.0_TDO_TB0OUTH_SMCLK_SRSCG1_21") (pintype "bidirectional"))
    )
    (net (code "85") (name "unconnected-(U2-PJ.3_TCK_COUT_SRCPUOFF-Pad24)") (class "Default")
      (node (ref "U2") (pin "24") (pinfunction "PJ.3_TCK_COUT_SRCPUOFF_24") (pintype "bidirectional"))
    )
    (net (code "86") (name "unconnected-(U4-AF-Pad14)") (class "Default")
      (node (ref "U4") (pin "14") (pinfunction "AF_14") (pintype "bidirectional"))
    )
    (net (code "87") (name "unconnected-(U4-IRQ2-Pad4)") (class "Default")
      (node (ref "U4") (pin "4") (pinfunction "IRQ2_4") (pintype "bidirectional"))
    )
    (net (code "88") (name "unconnected-(U4-TIRQ-Pad12)") (class "Default")
      (node (ref "U4") (pin "12") (pinfunction "TIRQ_12") (pintype "bidirectional"))
    )
    (net (code "89") (name "unconnected-(U4-XI-Pad16)") (class "Default")
      (node (ref "U4") (pin "16") (pinfunction "XI_16") (pintype "bidirectional"))
    )
    (net (code "90") (name "unconnected-(U4-XO-Pad15)") (class "Default")
      (node (ref "U4") (pin "15") (pinfunction "XO_15") (pintype "bidirectional"))
    )
    (net (code "91") (name "unconnected-(U5-HA-Pad15)") (class "Default")
      (node (ref "U5") (pin "15") (pinfunction "HA_15") (pintype "passive"))
    )
    (net (code "92") (name "unconnected-(U5-HB-Pad12)") (class "Default")
      (node (ref "U5") (pin "12") (pinfunction "HB_12") (pintype "bidirectional"))
    )
    (net (code "93") (name "~{CS}") (class "Default")
      (node (ref "IC1") (pin "7") (pinfunction "CSN_7") (pintype "bidirectional"))
      (node (ref "JP9") (pin "5") (pinfunction "5_5") (pintype "passive"))
    )
    (net (code "94") (name "~{P1_CS}") (class "Default")
      (node (ref "U2") (pin "6") (pinfunction "P2.4_TB0.3_6") (pintype "bidirectional"))
    )
    (net (code "95") (name "~{P2_CS}") (class "Default")
      (node (ref "JP6") (pin "5") (pinfunction "5_5") (pintype "passive"))
      (node (ref "U2") (pin "11") (pinfunction "P5.1_TA1.2_11") (pintype "bidirectional"))
    )
    (net (code "96") (name "~{P3_CS}") (class "Default")
      (node (ref "U2") (pin "23") (pinfunction "PJ.2_TMS_ACLK_SROSCOFF_23") (pintype "bidirectional"))
    )
  )
)
